# AST1042.net
KiCad netlist of a schematic drawn in EAGLE
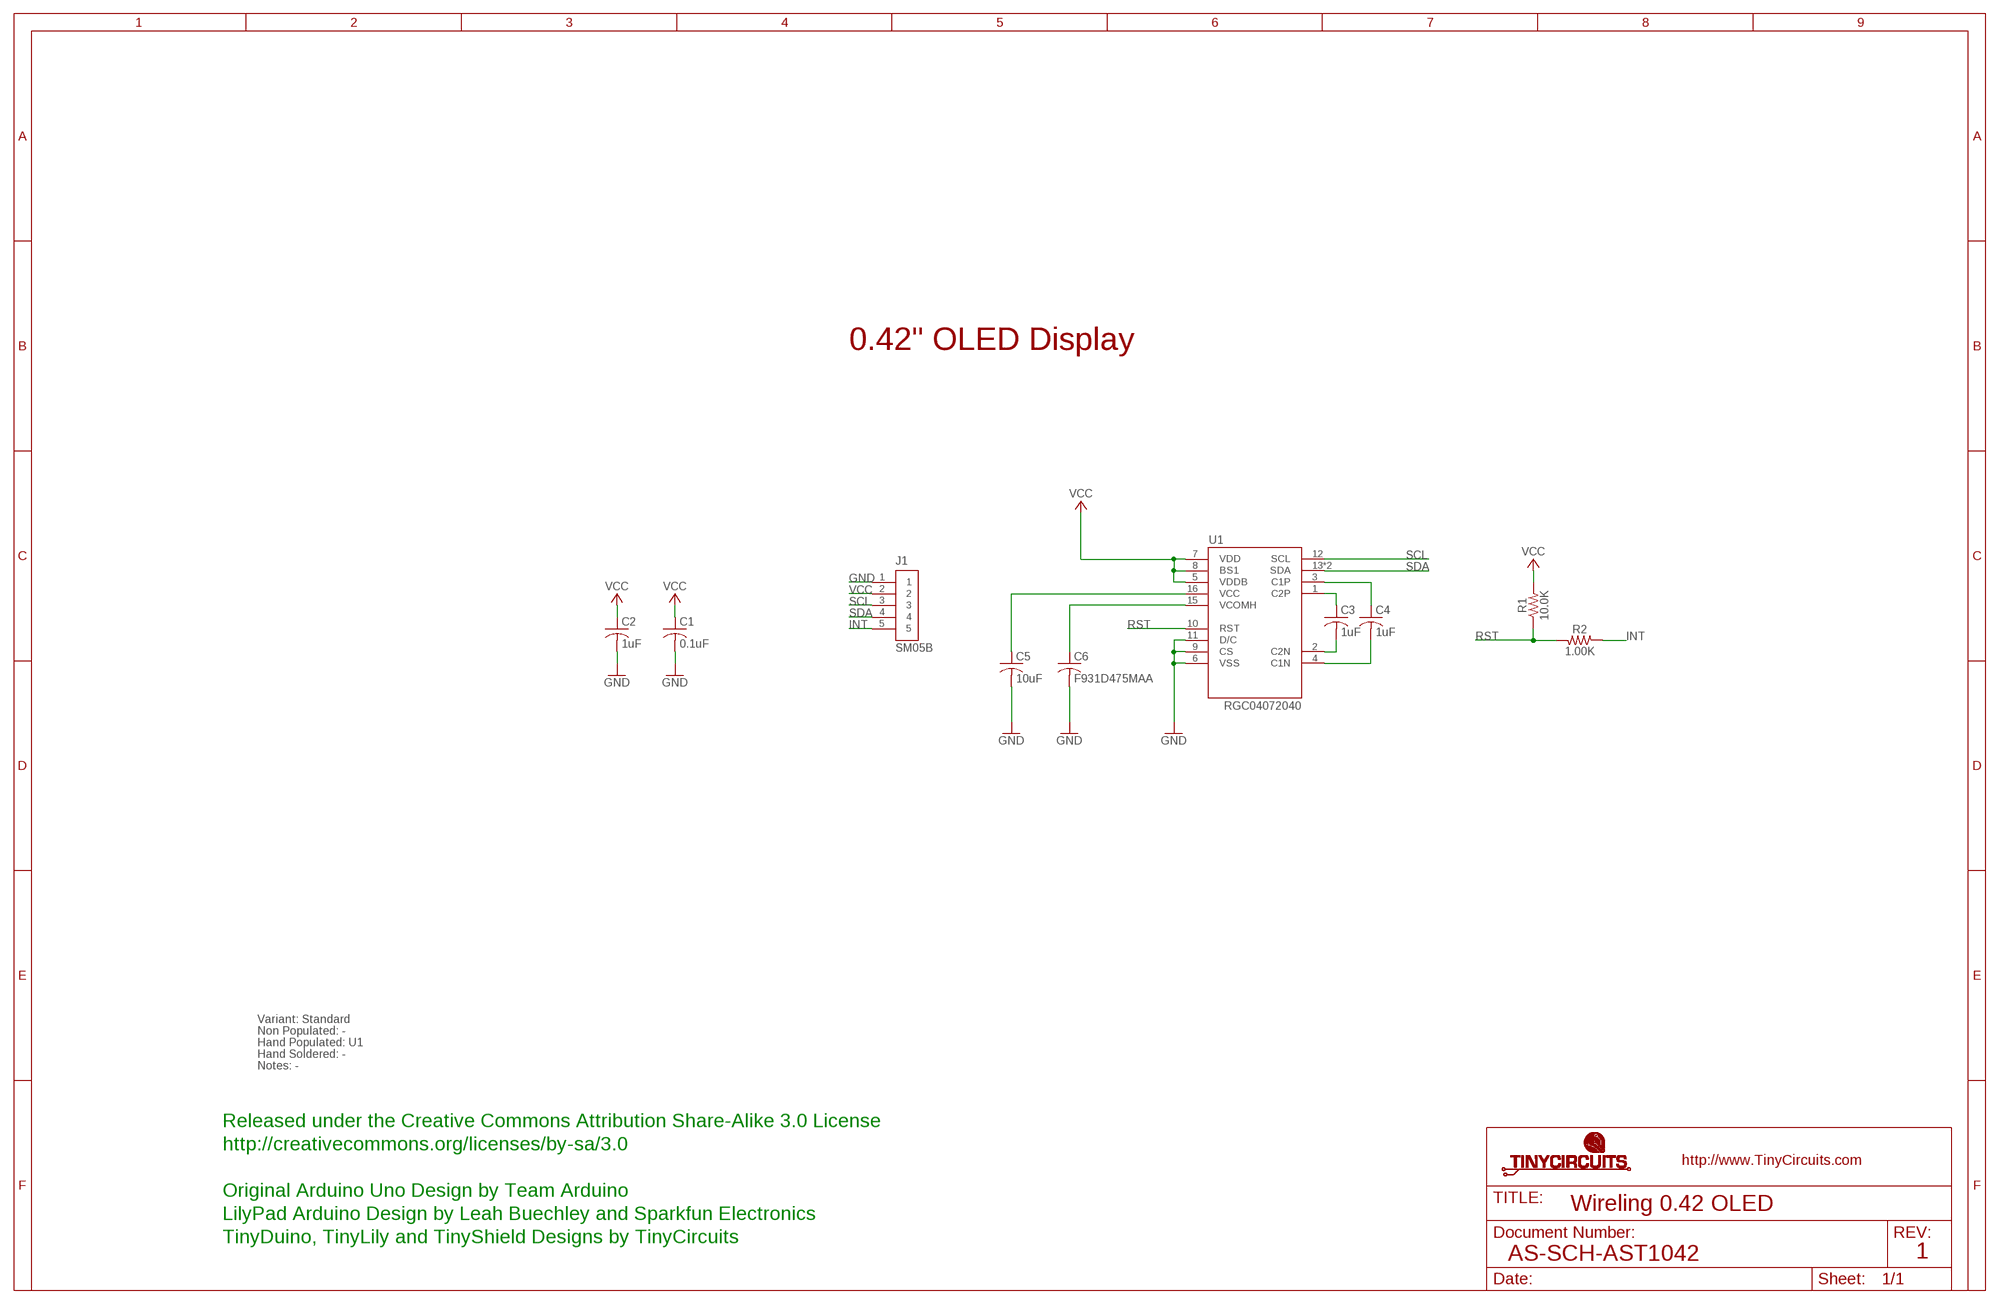
[diagram p0: schematic, sheet 1]

(export (version "E")
  (design (tool "Eeschema 10.0.6"))
  (components
    (comp (ref "C1")
      (value "0.1uF")
      (footprint "eagle-import:C0402")
      (fields (field (name "PARTNO") "AS-ITM-00008"))
      (libsource (lib "eagle-import") (part "AS-ITM-00008"))
    )
    (comp (ref "C2")
      (value "1uF")
      (footprint "eagle-import:C0603")
      (fields (field (name "PARTNO") "AS-ITM-00410") (field (name "PARTNO_1") "AS-ITM-00410"))
      (libsource (lib "eagle-import") (part "AS-ITM-00410"))
    )
    (comp (ref "C3")
      (value "1uF")
      (footprint "eagle-import:C0603")
      (fields (field (name "PARTNO") "AS-ITM-00347"))
      (libsource (lib "eagle-import") (part "AS-ITM-00347"))
    )
    (comp (ref "C4")
      (value "1uF")
      (footprint "eagle-import:C0603")
      (fields (field (name "PARTNO") "AS-ITM-00347"))
      (libsource (lib "eagle-import") (part "AS-ITM-00347"))
    )
    (comp (ref "C5")
      (value "10uF")
      (footprint "eagle-import:C0805")
      (fields (field (name "PARTNO") "AS-ITM-00045"))
      (libsource (lib "eagle-import") (part "AS-ITM-00045"))
    )
    (comp (ref "C6")
      (value "F931D475MAA")
      (footprint "eagle-import:1206_CAP_TANT")
      (fields (field (name "PARTNO") "AS-ITM-00232"))
      (libsource (lib "eagle-import") (part "AS-ITM-00232"))
    )
    (comp (ref "J1")
      (value "SM05B")
      (footprint "eagle-import:JST_SH_5X1_EDGE")
      (fields (field (name "PARTNO") "AS-ITM-00340"))
      (libsource (lib "eagle-import") (part "AS-ITM-00340EDGE"))
    )
    (comp (ref "R1")
      (value "10.0K")
      (footprint "eagle-import:0402")
      (fields (field (name "PARTNO") "AS-ITM-00032"))
      (libsource (lib "eagle-import") (part "AS-ITM-00032"))
    )
    (comp (ref "R2")
      (value "1.00K")
      (footprint "eagle-import:0402")
      (fields (field (name "PARTNO") "AS-ITM-00003") (field (name "PARTNO_1") "AS-ITM-00003"))
      (libsource (lib "eagle-import") (part "AS-ITM-00003"))
    )
    (comp (ref "U1")
      (value "RGC04072040")
      (footprint "eagle-import:OLED_042")
      (fields (field (name "PARTNO") "AS-ITM-00485"))
      (libsource (lib "eagle-import") (part "AS-ITM-00485"))
    )
  )
  (nets
    (net (code "1") (name "/INT") (class "Default")
      (node (ref "J1") (pin "5") (pinfunction "5_5") (pintype "bidirectional"))
      (node (ref "R2") (pin "1") (pinfunction "1_1") (pintype "passive"))
    )
    (net (code "2") (name "/RST") (class "Default")
      (node (ref "R1") (pin "1") (pinfunction "1_1") (pintype "passive"))
      (node (ref "R2") (pin "2") (pinfunction "2_2") (pintype "passive"))
      (node (ref "U1") (pin "10") (pinfunction "RST_10") (pintype "bidirectional"))
    )
    (net (code "3") (name "/SCL") (class "Default")
      (node (ref "J1") (pin "3") (pinfunction "3_3") (pintype "bidirectional"))
      (node (ref "U1") (pin "12") (pinfunction "SCL_12") (pintype "bidirectional"))
    )
    (net (code "4") (name "/SDA") (class "Default")
      (node (ref "J1") (pin "4") (pinfunction "4_4") (pintype "bidirectional"))
      (node (ref "U1") (pin "13") (pinfunction "SDA_13") (pintype "bidirectional"))
      (node (ref "U1") (pin "14") (pinfunction "SDA_14") (pintype "bidirectional"))
    )
    (net (code "5") (name "GND") (class "Default")
      (node (ref "C1") (pin "2") (pinfunction "2_2") (pintype "passive"))
      (node (ref "C2") (pin "2") (pinfunction "2_2") (pintype "passive"))
      (node (ref "C5") (pin "2") (pinfunction "2_2") (pintype "passive"))
      (node (ref "C6") (pin "2") (pinfunction "2_2") (pintype "passive"))
      (node (ref "J1") (pin "1") (pinfunction "1_1") (pintype "bidirectional"))
      (node (ref "U1") (pin "11") (pinfunction "D/C_11") (pintype "bidirectional"))
      (node (ref "U1") (pin "6") (pinfunction "VSS_6") (pintype "bidirectional"))
      (node (ref "U1") (pin "9") (pinfunction "CS_9") (pintype "bidirectional"))
    )
    (net (code "6") (name "Net-(U1-C1N)") (class "Default")
      (node (ref "C4") (pin "2") (pinfunction "2_2") (pintype "passive"))
      (node (ref "U1") (pin "4") (pinfunction "C1N_4") (pintype "bidirectional"))
    )
    (net (code "7") (name "Net-(U1-C1P)") (class "Default")
      (node (ref "C4") (pin "1") (pinfunction "1_1") (pintype "passive"))
      (node (ref "U1") (pin "3") (pinfunction "C1P_3") (pintype "bidirectional"))
    )
    (net (code "8") (name "Net-(U1-C2N)") (class "Default")
      (node (ref "C3") (pin "2") (pinfunction "2_2") (pintype "passive"))
      (node (ref "U1") (pin "2") (pinfunction "C2N_2") (pintype "bidirectional"))
    )
    (net (code "9") (name "Net-(U1-C2P)") (class "Default")
      (node (ref "C3") (pin "1") (pinfunction "1_1") (pintype "passive"))
      (node (ref "U1") (pin "1") (pinfunction "C2P_1") (pintype "bidirectional"))
    )
    (net (code "10") (name "Net-(U1-VCC)") (class "Default")
      (node (ref "C5") (pin "1") (pinfunction "1_1") (pintype "passive"))
      (node (ref "U1") (pin "16") (pinfunction "VCC_16") (pintype "bidirectional"))
    )
    (net (code "11") (name "Net-(U1-VCOMH)") (class "Default")
      (node (ref "C6") (pin "1") (pinfunction "1_1") (pintype "passive"))
      (node (ref "U1") (pin "15") (pinfunction "VCOMH_15") (pintype "bidirectional"))
    )
    (net (code "12") (name "VCC") (class "Default")
      (node (ref "C1") (pin "1") (pinfunction "1_1") (pintype "passive"))
      (node (ref "C2") (pin "1") (pinfunction "1_1") (pintype "passive"))
      (node (ref "J1") (pin "2") (pinfunction "2_2") (pintype "bidirectional"))
      (node (ref "R1") (pin "2") (pinfunction "2_2") (pintype "passive"))
      (node (ref "U1") (pin "5") (pinfunction "VDDB_5") (pintype "bidirectional"))
      (node (ref "U1") (pin "7") (pinfunction "VDD_7") (pintype "bidirectional"))
      (node (ref "U1") (pin "8") (pinfunction "BS1_8") (pintype "bidirectional"))
    )
  )
)
